# amc6821-breakout-v2_2.net
KiCad netlist of a schematic drawn in EAGLE
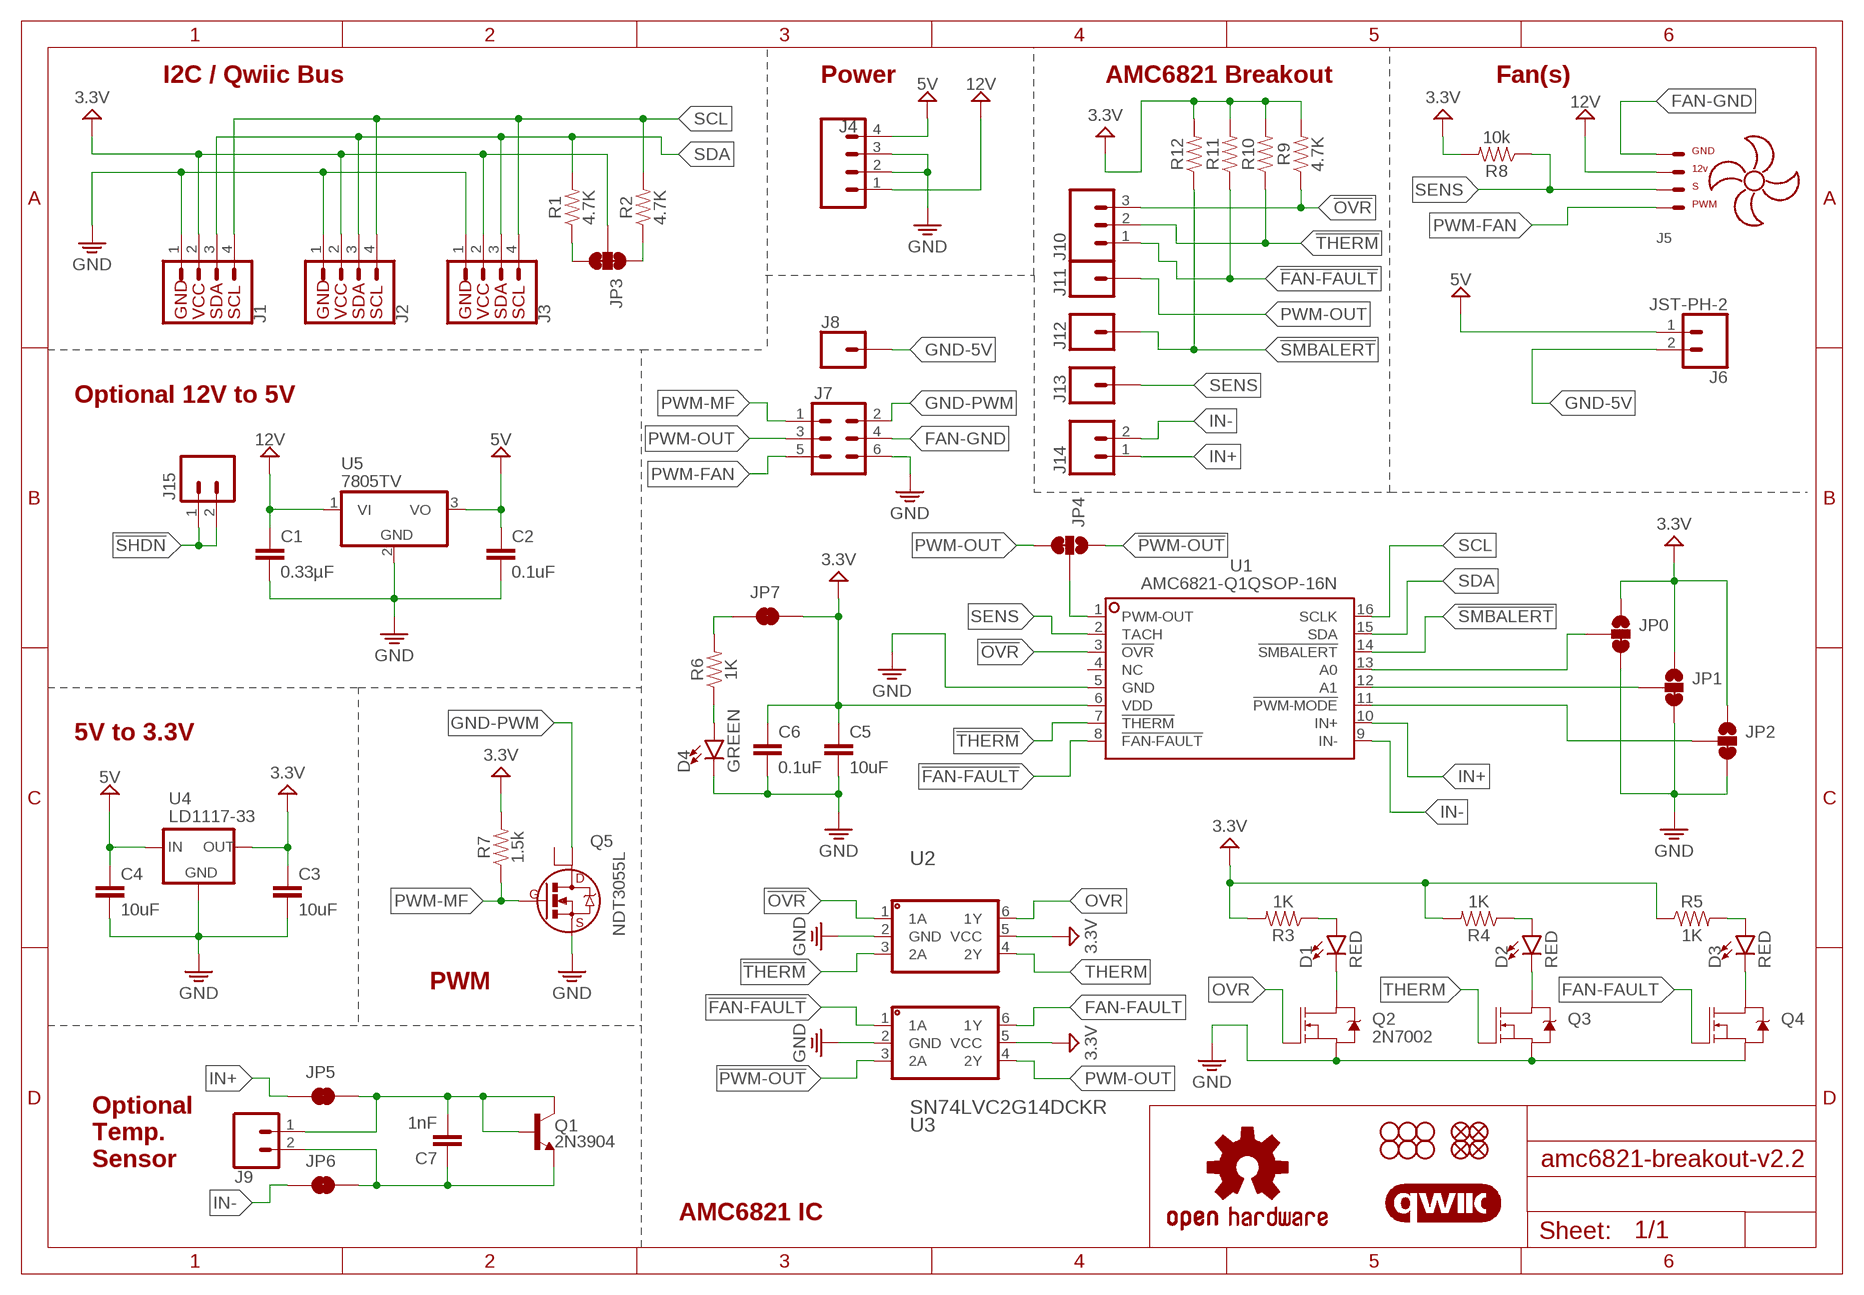
[diagram p0: schematic, sheet 1]

(export (version "E")
  (design (tool "Eeschema 10.0.6"))
  (components
    (comp (ref "C1")
      (value "0.33µF")
      (footprint "eagle-import:0805")
      (libsource (lib "eagle-import") (part "0.33UF/330NF-0805-50V-10%"))
    )
    (comp (ref "C2")
      (value "0.1uF")
      (footprint "eagle-import:0603")
      (libsource (lib "eagle-import") (part "0.1UF-0603-25V-5%"))
    )
    (comp (ref "C3")
      (value "10uF")
      (footprint "eagle-import:0603")
      (libsource (lib "eagle-import") (part "10UF-0603-6.3V-20%"))
    )
    (comp (ref "C4")
      (value "10uF")
      (footprint "eagle-import:0603")
      (libsource (lib "eagle-import") (part "10UF-0603-6.3V-20%"))
    )
    (comp (ref "C5")
      (value "10uF")
      (footprint "eagle-import:0603")
      (libsource (lib "eagle-import") (part "10UF-0603-6.3V-20%"))
    )
    (comp (ref "C6")
      (value "0.1uF")
      (footprint "eagle-import:0603")
      (libsource (lib "eagle-import") (part "0.1UF-0603-25V-5%"))
    )
    (comp (ref "C7")
      (value "1nF")
      (footprint "eagle-import:0603")
      (libsource (lib "eagle-import") (part "1.0NF/1000PF-0603-50V-10%"))
    )
    (comp (ref "D1")
      (value "RED")
      (footprint "eagle-import:LED-0603")
      (libsource (lib "eagle-import") (part "LED-RED0603"))
    )
    (comp (ref "D2")
      (value "RED")
      (footprint "eagle-import:LED-0603")
      (libsource (lib "eagle-import") (part "LED-RED0603"))
    )
    (comp (ref "D3")
      (value "RED")
      (footprint "eagle-import:LED-0603")
      (libsource (lib "eagle-import") (part "LED-RED0603"))
    )
    (comp (ref "D4")
      (value "GREEN")
      (footprint "eagle-import:LED-0603")
      (libsource (lib "eagle-import") (part "LED-GREEN0603"))
    )
    (comp (ref "FD1")
      (value "FIDUCIALUFIDUCIAL")
      (footprint "eagle-import:FIDUCIAL-MICRO")
      (libsource (lib "eagle-import") (part "FIDUCIALUFIDUCIAL"))
    )
    (comp (ref "FD2")
      (value "FIDUCIALUFIDUCIAL")
      (footprint "eagle-import:FIDUCIAL-MICRO")
      (libsource (lib "eagle-import") (part "FIDUCIALUFIDUCIAL"))
    )
    (comp (ref "FD3")
      (value "FIDUCIALUFIDUCIAL")
      (footprint "eagle-import:FIDUCIAL-MICRO")
      (libsource (lib "eagle-import") (part "FIDUCIALUFIDUCIAL"))
    )
    (comp (ref "FD4")
      (value "FIDUCIALUFIDUCIAL")
      (footprint "eagle-import:FIDUCIAL-MICRO")
      (libsource (lib "eagle-import") (part "FIDUCIALUFIDUCIAL"))
    )
    (comp (ref "H1")
      (value "STAND-OFF")
      (footprint "eagle-import:STAND-OFF")
      (libsource (lib "eagle-import") (part "STAND-OFF"))
    )
    (comp (ref "H2")
      (value "STAND-OFF")
      (footprint "eagle-import:STAND-OFF")
      (libsource (lib "eagle-import") (part "STAND-OFF"))
    )
    (comp (ref "H3")
      (value "STAND-OFF")
      (footprint "eagle-import:STAND-OFF")
      (libsource (lib "eagle-import") (part "STAND-OFF"))
    )
    (comp (ref "H4")
      (value "STAND-OFF")
      (footprint "eagle-import:STAND-OFF")
      (libsource (lib "eagle-import") (part "STAND-OFF"))
    )
    (comp (ref "H5")
      (value "STAND-OFF")
      (footprint "eagle-import:STAND-OFF")
      (libsource (lib "eagle-import") (part "STAND-OFF"))
    )
    (comp (ref "H6")
      (value "STAND-OFF")
      (footprint "eagle-import:STAND-OFF")
      (libsource (lib "eagle-import") (part "STAND-OFF"))
    )
    (comp (ref "J1")
      (value "QWIIC_RIGHT_ANGLE")
      (footprint "eagle-import:JST04_1MM_RA")
      (libsource (lib "eagle-import") (part "QWIIC_CONNECTORJS-1MM"))
    )
    (comp (ref "J2")
      (value "QWIIC_RIGHT_ANGLE")
      (footprint "eagle-import:JST04_1MM_RA")
      (libsource (lib "eagle-import") (part "QWIIC_CONNECTORJS-1MM"))
    )
    (comp (ref "J3")
      (value "I2C_STANDARD")
      (footprint "eagle-import:1X04")
      (libsource (lib "eagle-import") (part "I2C_STANDARD"))
    )
    (comp (ref "J4")
      (value "CONN_04SCREW")
      (footprint "eagle-import:SCREWTERMINAL-3.5MM-4")
      (libsource (lib "eagle-import") (part "CONN_04SCREW"))
    )
    (comp (ref "J5")
      (value "KK-254-4KK-254")
      (footprint "eagle-import:MOLEX_47053-1000")
      (libsource (lib "eagle-import") (part "KK-254-4KK-254"))
    )
    (comp (ref "J6")
      (value "JST-PH-2")
      (footprint "eagle-import:JST-PH2")
      (libsource (lib "eagle-import") (part "JST-PH-2"))
    )
    (comp (ref "J7")
      (value "CONN_03X2NO_SILK")
      (footprint "eagle-import:2X3-NS")
      (libsource (lib "eagle-import") (part "CONN_03X2NO_SILK"))
    )
    (comp (ref "J8")
      (value "CONN_01")
      (footprint "eagle-import:1X01")
      (libsource (lib "eagle-import") (part "CONN_01"))
    )
    (comp (ref "J9")
      (value "CONN_02")
      (footprint "eagle-import:1X02")
      (libsource (lib "eagle-import") (part "CONN_02"))
    )
    (comp (ref "J10")
      (value "455-1750-1-ND")
      (footprint "eagle-import:1X03")
      (libsource (lib "eagle-import") (part "CONN_03"))
    )
    (comp (ref "J11")
      (value "CONN_01")
      (footprint "eagle-import:1X01")
      (libsource (lib "eagle-import") (part "CONN_01"))
    )
    (comp (ref "J12")
      (value "CONN_01")
      (footprint "eagle-import:1X01")
      (libsource (lib "eagle-import") (part "CONN_01"))
    )
    (comp (ref "J13")
      (value "CONN_01")
      (footprint "eagle-import:1X01")
      (libsource (lib "eagle-import") (part "CONN_01"))
    )
    (comp (ref "J14")
      (value "CONN_02")
      (footprint "eagle-import:1X02")
      (libsource (lib "eagle-import") (part "CONN_02"))
    )
    (comp (ref "J15")
      (value "CONN_021X02_NO_SILK")
      (footprint "eagle-import:1X02_NO_SILK")
      (libsource (lib "eagle-import") (part "CONN_021X02_NO_SILK"))
    )
    (comp (ref "JP0")
      (value "JUMPER-SMT_3_1-NC_TRACE_SILK")
      (footprint "eagle-import:SMT-JUMPER_3_1-NC_TRACE_SILK")
      (libsource (lib "eagle-import") (part "JUMPER-SMT_3_1-NC_TRACE_SILK"))
    )
    (comp (ref "JP1")
      (value "JUMPER-SMT_3_1-NC_TRACE_SILK")
      (footprint "eagle-import:SMT-JUMPER_3_1-NC_TRACE_SILK")
      (libsource (lib "eagle-import") (part "JUMPER-SMT_3_1-NC_TRACE_SILK"))
    )
    (comp (ref "JP2")
      (value "JUMPER-SMT_3_1-NC_TRACE_SILK")
      (footprint "eagle-import:SMT-JUMPER_3_1-NC_TRACE_SILK")
      (libsource (lib "eagle-import") (part "JUMPER-SMT_3_1-NC_TRACE_SILK"))
    )
    (comp (ref "JP3")
      (value "JUMPER-SMT_3_2-NC_TRACE_SILK")
      (footprint "eagle-import:SMT-JUMPER_3_2-NC_TRACE_SILK")
      (libsource (lib "eagle-import") (part "JUMPER-SMT_3_2-NC_TRACE_SILK"))
    )
    (comp (ref "JP4")
      (value "JUMPER-SMT_3_1-NC_TRACE_SILK")
      (footprint "eagle-import:SMT-JUMPER_3_1-NC_TRACE_SILK")
      (libsource (lib "eagle-import") (part "JUMPER-SMT_3_1-NC_TRACE_SILK"))
    )
    (comp (ref "JP5")
      (value "JUMPER-SMT_2_NC_TRACE_SILK")
      (footprint "eagle-import:SMT-JUMPER_2_NC_TRACE_SILK")
      (libsource (lib "eagle-import") (part "JUMPER-SMT_2_NC_TRACE_SILK"))
    )
    (comp (ref "JP6")
      (value "JUMPER-SMT_2_NC_TRACE_SILK")
      (footprint "eagle-import:SMT-JUMPER_2_NC_TRACE_SILK")
      (libsource (lib "eagle-import") (part "JUMPER-SMT_2_NC_TRACE_SILK"))
    )
    (comp (ref "JP7")
      (value "JUMPER-SMT_2_NC_TRACE_SILK")
      (footprint "eagle-import:SMT-JUMPER_2_NC_TRACE_SILK")
      (libsource (lib "eagle-import") (part "JUMPER-SMT_2_NC_TRACE_SILK"))
    )
    (comp (ref "LOGO1")
      (value "OSHW-LOGOS")
      (footprint "eagle-import:OSHW-LOGO-S")
      (libsource (lib "eagle-import") (part "OSHW-LOGOS"))
    )
    (comp (ref "LOGO2")
      (value "QWIIC_LOGO_6MM")
      (footprint "eagle-import:QWIIC_6MM")
      (libsource (lib "eagle-import") (part "QWIIC_LOGO_6MM"))
    )
    (comp (ref "Q1")
      (value "2N3904")
      (footprint "eagle-import:SOT23-3")
      (libsource (lib "eagle-import") (part "TRANS_NPN-MMBTA42"))
    )
    (comp (ref "Q2")
      (value "2N7002")
      (footprint "eagle-import:SOT23-3")
      (libsource (lib "eagle-import") (part "2N7002-BSS138"))
    )
    (comp (ref "Q3")
      (value "2N7002-BSS138")
      (footprint "eagle-import:SOT23-3")
      (libsource (lib "eagle-import") (part "2N7002-BSS138"))
    )
    (comp (ref "Q4")
      (value "2N7002-BSS138")
      (footprint "eagle-import:SOT23-3")
      (libsource (lib "eagle-import") (part "2N7002-BSS138"))
    )
    (comp (ref "Q5")
      (value "NDT3055L")
      (footprint "eagle-import:SOT223")
      (libsource (lib "eagle-import") (part "NDT3055L"))
    )
    (comp (ref "R1")
      (value "4.7K")
      (footprint "eagle-import:0805")
      (libsource (lib "eagle-import") (part "RESISTOR0805"))
    )
    (comp (ref "R2")
      (value "4.7K")
      (footprint "eagle-import:0805")
      (libsource (lib "eagle-import") (part "RESISTOR0805"))
    )
    (comp (ref "R3")
      (value "1K")
      (footprint "eagle-import:0805")
      (libsource (lib "eagle-import") (part "RESISTOR0805"))
    )
    (comp (ref "R4")
      (value "1K")
      (footprint "eagle-import:0805")
      (libsource (lib "eagle-import") (part "RESISTOR0805"))
    )
    (comp (ref "R5")
      (value "1K")
      (footprint "eagle-import:0805")
      (libsource (lib "eagle-import") (part "RESISTOR0805"))
    )
    (comp (ref "R6")
      (value "1K")
      (footprint "eagle-import:0805")
      (libsource (lib "eagle-import") (part "RESISTOR0805"))
    )
    (comp (ref "R7")
      (value "1.5k")
      (footprint "eagle-import:0603")
      (libsource (lib "eagle-import") (part "1.5KOHM-0603-1/10W-1%"))
    )
    (comp (ref "R8")
      (value "10k")
      (footprint "eagle-import:0603")
      (libsource (lib "eagle-import") (part "10KOHM-0603-1/10W-1%"))
    )
    (comp (ref "R9")
      (value "4.7K")
      (footprint "eagle-import:0805")
      (libsource (lib "eagle-import") (part "RESISTOR0805"))
    )
    (comp (ref "R10")
      (value "4.7K")
      (footprint "eagle-import:0805")
      (libsource (lib "eagle-import") (part "RESISTOR0805"))
    )
    (comp (ref "R11")
      (value "4.7K")
      (footprint "eagle-import:0805")
      (libsource (lib "eagle-import") (part "RESISTOR0805"))
    )
    (comp (ref "R12")
      (value "4.7K")
      (footprint "eagle-import:0805")
      (libsource (lib "eagle-import") (part "RESISTOR0805"))
    )
    (comp (ref "U1")
      (value "AMC6821-Q1QSOP-16N")
      (footprint "eagle-import:QSOP-16N")
      (libsource (lib "eagle-import") (part "AMC6821-Q1QSOP-16N"))
    )
    (comp (ref "U2")
      (value "SN74LVC2G14DCKR")
      (footprint "eagle-import:SOT65P210X110-6N")
      (libsource (lib "eagle-import") (part "SN74LVC2G14DCKR"))
    )
    (comp (ref "U3")
      (value "SN74LVC2G14DCKR")
      (footprint "eagle-import:SOT65P210X110-6N")
      (libsource (lib "eagle-import") (part "SN74LVC2G14DCKR"))
    )
    (comp (ref "U4")
      (value "LD1117-33")
      (footprint "eagle-import:SOT223")
      (libsource (lib "eagle-import") (part "V_REG_LD1117VXXLD1117-SMD"))
    )
    (comp (ref "U5")
      (value "7805TV")
      (footprint "eagle-import:TO220V")
      (libsource (lib "eagle-import") (part "78TV05"))
    )
  )
  (nets
    (net (code "1") (name "/~{FAN-FAULT}") (class "Default")
      (node (ref "J10") (pin "1") (pinfunction "1_1") (pintype "passive"))
      (node (ref "R11") (pin "1") (pinfunction "1_1") (pintype "passive"))
      (node (ref "U1") (pin "8") (pinfunction "~{FAN-FAULT}_8") (pintype "output"))
      (node (ref "U3") (pin "1") (pinfunction "1A_1") (pintype "input"))
    )
    (net (code "2") (name "/~{OVR}") (class "Default")
      (node (ref "J10") (pin "3") (pinfunction "3_3") (pintype "passive"))
      (node (ref "R9") (pin "1") (pinfunction "1_1") (pintype "passive"))
      (node (ref "U1") (pin "3") (pinfunction "~{OVR}_3") (pintype "output"))
      (node (ref "U2") (pin "1") (pinfunction "1A_1") (pintype "input"))
    )
    (net (code "3") (name "/~{PWM-OUT}") (class "Default")
      (node (ref "JP4") (pin "1") (pinfunction "1_1") (pintype "passive"))
      (node (ref "U3") (pin "3") (pinfunction "2A_3") (pintype "input"))
    )
    (net (code "4") (name "/~{SHDN}") (class "Default")
      (node (ref "J15") (pin "1") (pinfunction "1_1") (pintype "passive"))
      (node (ref "J15") (pin "2") (pinfunction "2_2") (pintype "passive"))
    )
    (net (code "5") (name "/~{SMBALERT}") (class "Default")
      (node (ref "J12") (pin "1") (pinfunction "1_1") (pintype "passive"))
      (node (ref "R12") (pin "1") (pinfunction "1_1") (pintype "passive"))
      (node (ref "U1") (pin "14") (pinfunction "~{SMBALERT}_14") (pintype "input"))
    )
    (net (code "6") (name "/~{THERM}") (class "Default")
      (node (ref "J10") (pin "2") (pinfunction "2_2") (pintype "passive"))
      (node (ref "R10") (pin "1") (pinfunction "1_1") (pintype "passive"))
      (node (ref "U1") (pin "7") (pinfunction "~{THERM}_7") (pintype "bidirectional"))
      (node (ref "U2") (pin "3") (pinfunction "2A_3") (pintype "input"))
    )
    (net (code "7") (name "3.3V") (class "Default")
      (node (ref "C3") (pin "1") (pinfunction "1_1") (pintype "passive"))
      (node (ref "C5") (pin "1") (pinfunction "1_1") (pintype "passive"))
      (node (ref "C6") (pin "1") (pinfunction "1_1") (pintype "passive"))
      (node (ref "J1") (pin "2") (pinfunction "2_2") (pintype "power_in"))
      (node (ref "J2") (pin "2") (pinfunction "2_2") (pintype "power_in"))
      (node (ref "J3") (pin "2") (pinfunction "2_2") (pintype "power_in"))
      (node (ref "JP0") (pin "1") (pinfunction "1_1") (pintype "passive"))
      (node (ref "JP1") (pin "1") (pinfunction "1_1") (pintype "passive"))
      (node (ref "JP2") (pin "1") (pinfunction "1_1") (pintype "passive"))
      (node (ref "JP3") (pin "2") (pinfunction "2_2") (pintype "passive"))
      (node (ref "JP7") (pin "2") (pinfunction "2_2") (pintype "passive"))
      (node (ref "R10") (pin "2") (pinfunction "2_2") (pintype "passive"))
      (node (ref "R11") (pin "2") (pinfunction "2_2") (pintype "passive"))
      (node (ref "R12") (pin "2") (pinfunction "2_2") (pintype "passive"))
      (node (ref "R3") (pin "2") (pinfunction "2_2") (pintype "passive"))
      (node (ref "R4") (pin "2") (pinfunction "2_2") (pintype "passive"))
      (node (ref "R5") (pin "1") (pinfunction "1_1") (pintype "passive"))
      (node (ref "R7") (pin "2") (pinfunction "2_2") (pintype "passive"))
      (node (ref "R8") (pin "2") (pinfunction "2_2") (pintype "passive"))
      (node (ref "R9") (pin "2") (pinfunction "2_2") (pintype "passive"))
      (node (ref "U1") (pin "6") (pinfunction "VDD_6") (pintype "power_in"))
      (node (ref "U2") (pin "5") (pinfunction "VCC_5") (pintype "power_in"))
      (node (ref "U3") (pin "5") (pinfunction "VCC_5") (pintype "power_in"))
      (node (ref "U4") (pin "2") (pinfunction "OUT_2") (pintype "passive"))
    )
    (net (code "8") (name "5V") (class "Default")
      (node (ref "C2") (pin "1") (pinfunction "1_1") (pintype "passive"))
      (node (ref "C4") (pin "1") (pinfunction "1_1") (pintype "passive"))
      (node (ref "J4") (pin "4") (pinfunction "4_4") (pintype "passive"))
      (node (ref "J6") (pin "1") (pinfunction "1_1") (pintype "passive"))
      (node (ref "U4") (pin "3") (pinfunction "IN_3") (pintype "input"))
      (node (ref "U5") (pin "3") (pinfunction "VO_3") (pintype "passive"))
    )
    (net (code "9") (name "12V") (class "Default")
      (node (ref "C1") (pin "1") (pinfunction "1_1") (pintype "passive"))
      (node (ref "J4") (pin "1") (pinfunction "1_1") (pintype "passive"))
      (node (ref "J5") (pin "2:+12VDC") (pinfunction "2:+12VDC_2:+12VDC") (pintype "power_in"))
      (node (ref "U5") (pin "1") (pinfunction "VI_1") (pintype "input"))
    )
    (net (code "10") (name "FAN-FAULT") (class "Default")
      (node (ref "Q4") (pin "1") (pinfunction "G_1") (pintype "bidirectional"))
      (node (ref "U3") (pin "6") (pinfunction "1Y_6") (pintype "output"))
    )
    (net (code "11") (name "FAN-GND") (class "Default")
      (node (ref "J5") (pin "1:GND") (pinfunction "1:GND_1:GND") (pintype "power_in"))
      (node (ref "J7") (pin "4") (pinfunction "4_4") (pintype "bidirectional"))
    )
    (net (code "12") (name "GND") (class "Default")
      (node (ref "C1") (pin "2") (pinfunction "2_2") (pintype "passive"))
      (node (ref "C2") (pin "2") (pinfunction "2_2") (pintype "passive"))
      (node (ref "C3") (pin "2") (pinfunction "2_2") (pintype "passive"))
      (node (ref "C4") (pin "2") (pinfunction "2_2") (pintype "passive"))
      (node (ref "C5") (pin "2") (pinfunction "2_2") (pintype "passive"))
      (node (ref "C6") (pin "2") (pinfunction "2_2") (pintype "passive"))
      (node (ref "D4") (pin "C") (pinfunction "C_C") (pintype "passive"))
      (node (ref "J1") (pin "1") (pinfunction "1_1") (pintype "power_in"))
      (node (ref "J2") (pin "1") (pinfunction "1_1") (pintype "power_in"))
      (node (ref "J3") (pin "1") (pinfunction "1_1") (pintype "power_in"))
      (node (ref "J4") (pin "2") (pinfunction "2_2") (pintype "passive"))
      (node (ref "J4") (pin "3") (pinfunction "3_3") (pintype "passive"))
      (node (ref "J7") (pin "6") (pinfunction "6_6") (pintype "bidirectional"))
      (node (ref "JP0") (pin "3") (pinfunction "3_3") (pintype "passive"))
      (node (ref "JP1") (pin "3") (pinfunction "3_3") (pintype "passive"))
      (node (ref "JP2") (pin "3") (pinfunction "3_3") (pintype "passive"))
      (node (ref "Q2") (pin "2") (pinfunction "S_2") (pintype "bidirectional"))
      (node (ref "Q3") (pin "2") (pinfunction "S_2") (pintype "bidirectional"))
      (node (ref "Q4") (pin "2") (pinfunction "S_2") (pintype "bidirectional"))
      (node (ref "Q5") (pin "S") (pinfunction "S_S") (pintype "passive"))
      (node (ref "U1") (pin "5") (pinfunction "GND_5") (pintype "power_in"))
      (node (ref "U2") (pin "2") (pinfunction "GND_2") (pintype "passive"))
      (node (ref "U3") (pin "2") (pinfunction "GND_2") (pintype "passive"))
      (node (ref "U4") (pin "1") (pinfunction "GND_1") (pintype "input"))
      (node (ref "U5") (pin "2") (pinfunction "GND_2") (pintype "passive"))
    )
    (net (code "13") (name "GND-5V") (class "Default")
      (node (ref "J6") (pin "2") (pinfunction "2_2") (pintype "passive"))
      (node (ref "J8") (pin "1") (pinfunction "1_1") (pintype "passive"))
    )
    (net (code "14") (name "GND-PWM") (class "Default")
      (node (ref "J7") (pin "2") (pinfunction "2_2") (pintype "bidirectional"))
      (node (ref "Q5") (pin "D") (pinfunction "D_D") (pintype "passive"))
    )
    (net (code "15") (name "IN+") (class "Default")
      (node (ref "J14") (pin "1") (pinfunction "1_1") (pintype "passive"))
      (node (ref "JP5") (pin "1") (pinfunction "1_1") (pintype "passive"))
      (node (ref "U1") (pin "10") (pinfunction "IN+_10") (pintype "output"))
    )
    (net (code "16") (name "IN-") (class "Default")
      (node (ref "J14") (pin "2") (pinfunction "2_2") (pintype "passive"))
      (node (ref "JP6") (pin "1") (pinfunction "1_1") (pintype "passive"))
      (node (ref "U1") (pin "9") (pinfunction "IN-_9") (pintype "input"))
    )
    (net (code "17") (name "Net-(D1-PadA)") (class "Default")
      (node (ref "D1") (pin "A") (pinfunction "A_A") (pintype "passive"))
      (node (ref "R3") (pin "1") (pinfunction "1_1") (pintype "passive"))
    )
    (net (code "18") (name "Net-(D2-PadA)") (class "Default")
      (node (ref "D2") (pin "A") (pinfunction "A_A") (pintype "passive"))
      (node (ref "R4") (pin "1") (pinfunction "1_1") (pintype "passive"))
    )
    (net (code "19") (name "Net-(D3-PadA)") (class "Default")
      (node (ref "D3") (pin "A") (pinfunction "A_A") (pintype "passive"))
      (node (ref "R5") (pin "2") (pinfunction "2_2") (pintype "passive"))
    )
    (net (code "20") (name "Net-(D4-PadA)") (class "Default")
      (node (ref "D4") (pin "A") (pinfunction "A_A") (pintype "passive"))
      (node (ref "R6") (pin "1") (pinfunction "1_1") (pintype "passive"))
    )
    (net (code "21") (name "Net-(JP3-Pad1)") (class "Default")
      (node (ref "JP3") (pin "1") (pinfunction "1_1") (pintype "passive"))
      (node (ref "R2") (pin "1") (pinfunction "1_1") (pintype "passive"))
    )
    (net (code "22") (name "Net-(JP3-Pad3)") (class "Default")
      (node (ref "JP3") (pin "3") (pinfunction "3_3") (pintype "passive"))
      (node (ref "R1") (pin "1") (pinfunction "1_1") (pintype "passive"))
    )
    (net (code "23") (name "Net-(JP7-Pad1)") (class "Default")
      (node (ref "JP7") (pin "1") (pinfunction "1_1") (pintype "passive"))
      (node (ref "R6") (pin "2") (pinfunction "2_2") (pintype "passive"))
    )
    (net (code "24") (name "Net-(Q1-B)") (class "Default")
      (node (ref "C7") (pin "2") (pinfunction "2_2") (pintype "passive"))
      (node (ref "J9") (pin "1") (pinfunction "1_1") (pintype "passive"))
      (node (ref "JP5") (pin "2") (pinfunction "2_2") (pintype "passive"))
      (node (ref "Q1") (pin "1") (pinfunction "B_1") (pintype "passive"))
      (node (ref "Q1") (pin "3") (pinfunction "C_3") (pintype "passive"))
    )
    (net (code "25") (name "Net-(Q1-E)") (class "Default")
      (node (ref "C7") (pin "1") (pinfunction "1_1") (pintype "passive"))
      (node (ref "J9") (pin "2") (pinfunction "2_2") (pintype "passive"))
      (node (ref "JP6") (pin "2") (pinfunction "2_2") (pintype "passive"))
      (node (ref "Q1") (pin "2") (pinfunction "E_2") (pintype "passive"))
    )
    (net (code "26") (name "Net-(Q2-D)") (class "Default")
      (node (ref "D1") (pin "C") (pinfunction "C_C") (pintype "passive"))
      (node (ref "Q2") (pin "3") (pinfunction "D_3") (pintype "bidirectional"))
    )
    (net (code "27") (name "Net-(Q3-D)") (class "Default")
      (node (ref "D2") (pin "C") (pinfunction "C_C") (pintype "passive"))
      (node (ref "Q3") (pin "3") (pinfunction "D_3") (pintype "bidirectional"))
    )
    (net (code "28") (name "Net-(Q4-D)") (class "Default")
      (node (ref "D3") (pin "C") (pinfunction "C_C") (pintype "passive"))
      (node (ref "Q4") (pin "3") (pinfunction "D_3") (pintype "bidirectional"))
    )
    (net (code "29") (name "Net-(U1-A0)") (class "Default")
      (node (ref "JP0") (pin "2") (pinfunction "2_2") (pintype "passive"))
      (node (ref "U1") (pin "13") (pinfunction "A0_13") (pintype "input"))
    )
    (net (code "30") (name "Net-(U1-A1)") (class "Default")
      (node (ref "JP1") (pin "2") (pinfunction "2_2") (pintype "passive"))
      (node (ref "U1") (pin "12") (pinfunction "A1_12") (pintype "input"))
    )
    (net (code "31") (name "Net-(U1-PWM-OUT)") (class "Default")
      (node (ref "JP4") (pin "2") (pinfunction "2_2") (pintype "passive"))
      (node (ref "U1") (pin "1") (pinfunction "PWM-OUT_1") (pintype "output"))
    )
    (net (code "32") (name "Net-(U1-~{PWM-MODE})") (class "Default")
      (node (ref "JP2") (pin "2") (pinfunction "2_2") (pintype "passive"))
      (node (ref "U1") (pin "11") (pinfunction "~{PWM-MODE}_11") (pintype "input"))
    )
    (net (code "33") (name "OVR") (class "Default")
      (node (ref "Q2") (pin "1") (pinfunction "G_1") (pintype "bidirectional"))
      (node (ref "U2") (pin "6") (pinfunction "1Y_6") (pintype "output"))
    )
    (net (code "34") (name "PWM-FAN") (class "Default")
      (node (ref "J5") (pin "4:PWM") (pinfunction "4:PWM_4:PWM") (pintype "output"))
      (node (ref "J7") (pin "5") (pinfunction "5_5") (pintype "bidirectional"))
    )
    (net (code "35") (name "PWM-MF") (class "Default")
      (node (ref "J7") (pin "1") (pinfunction "1_1") (pintype "bidirectional"))
      (node (ref "Q5") (pin "G") (pinfunction "G_G") (pintype "passive"))
      (node (ref "R7") (pin "1") (pinfunction "1_1") (pintype "passive"))
    )
    (net (code "36") (name "PWM-OUT") (class "Default")
      (node (ref "J11") (pin "1") (pinfunction "1_1") (pintype "passive"))
      (node (ref "J7") (pin "3") (pinfunction "3_3") (pintype "bidirectional"))
      (node (ref "JP4") (pin "3") (pinfunction "3_3") (pintype "passive"))
      (node (ref "U3") (pin "4") (pinfunction "2Y_4") (pintype "output"))
    )
    (net (code "37") (name "SCL") (class "Default")
      (node (ref "J1") (pin "4") (pinfunction "4_4") (pintype "passive"))
      (node (ref "J2") (pin "4") (pinfunction "4_4") (pintype "passive"))
      (node (ref "J3") (pin "4") (pinfunction "4_4") (pintype "passive"))
      (node (ref "R2") (pin "2") (pinfunction "2_2") (pintype "passive"))
      (node (ref "U1") (pin "16") (pinfunction "SCLK_16") (pintype "input"))
    )
    (net (code "38") (name "SDA") (class "Default")
      (node (ref "J1") (pin "3") (pinfunction "3_3") (pintype "passive"))
      (node (ref "J2") (pin "3") (pinfunction "3_3") (pintype "passive"))
      (node (ref "J3") (pin "3") (pinfunction "3_3") (pintype "passive"))
      (node (ref "R1") (pin "2") (pinfunction "2_2") (pintype "passive"))
      (node (ref "U1") (pin "15") (pinfunction "SDA_15") (pintype "bidirectional"))
    )
    (net (code "39") (name "SENS") (class "Default")
      (node (ref "J13") (pin "1") (pinfunction "1_1") (pintype "passive"))
      (node (ref "J5") (pin "3:TACH") (pinfunction "3:TACH_3:TACH") (pintype "input"))
      (node (ref "R8") (pin "1") (pinfunction "1_1") (pintype "passive"))
      (node (ref "U1") (pin "2") (pinfunction "TACH_2") (pintype "input"))
    )
    (net (code "40") (name "THERM") (class "Default")
      (node (ref "Q3") (pin "1") (pinfunction "G_1") (pintype "bidirectional"))
      (node (ref "U2") (pin "4") (pinfunction "2Y_4") (pintype "output"))
    )
    (net (code "41") (name "unconnected-(Q5-PadD2)") (class "Default")
      (node (ref "Q5") (pin "D2") (pinfunction "D2_D2") (pintype "passive"))
    )
    (net (code "42") (name "unconnected-(U1-NC-Pad4)") (class "Default")
      (node (ref "U1") (pin "4") (pinfunction "NC_4") (pintype "no_connect"))
    )
  )
)
